# Smart_Plug_Upadated01.net
KiCad netlist of a schematic drawn in Altium Designer
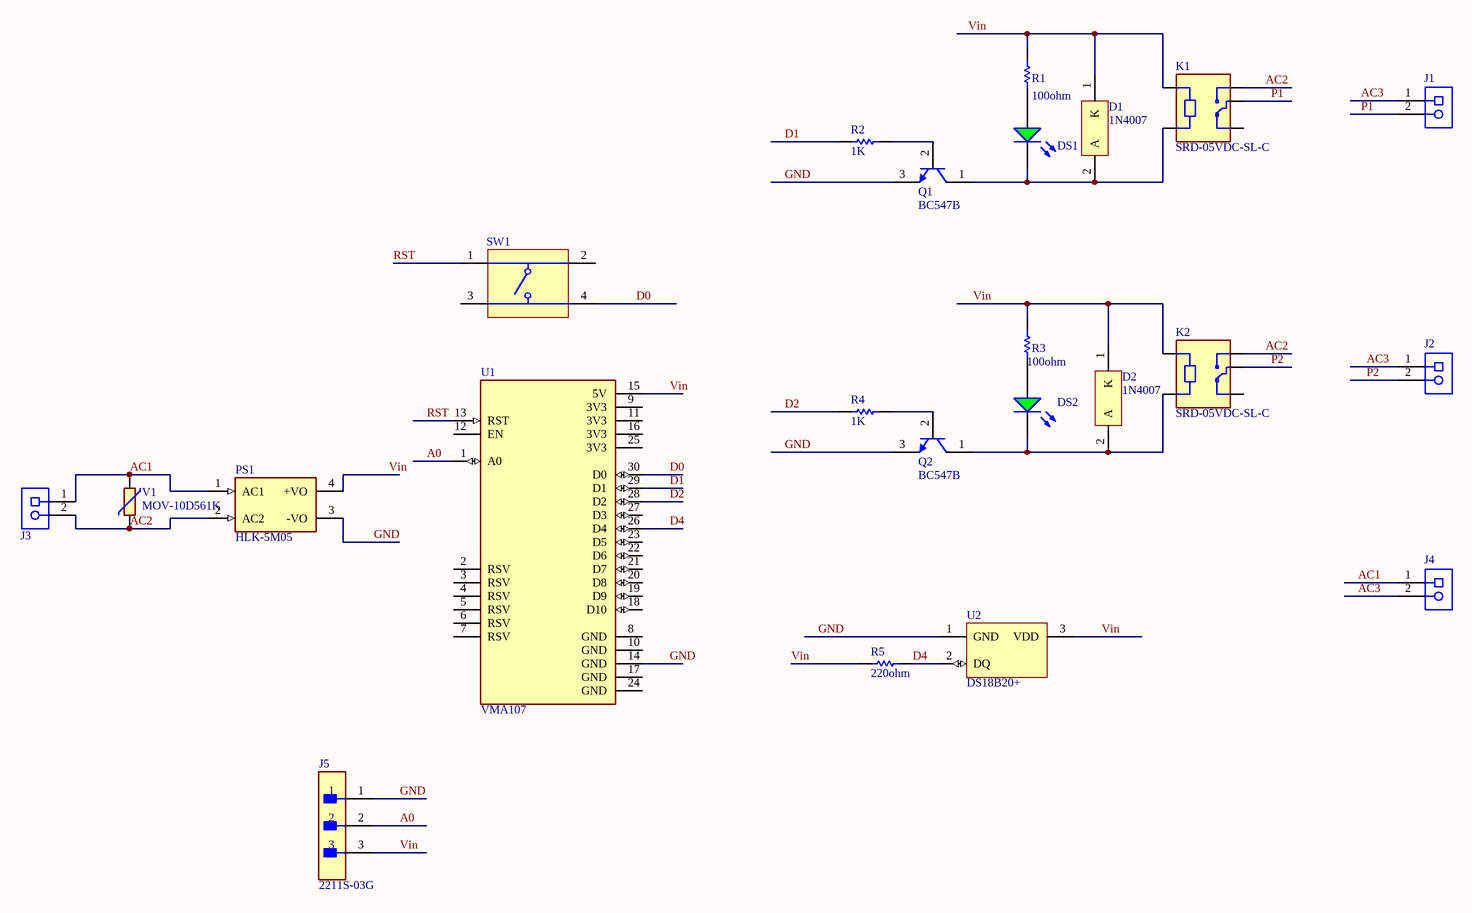
[diagram p0: Smart_Plug(Upadated01).SchDoc]

(export (version "E")
  (design (tool "Eeschema 10.0.6"))
  (components
    (comp (ref "D1")
      (value "1N4007")
      (footprint "ONSC-AXIAL_LEAD-2-59-10_P")
      (description "Standard Recovery Rectifier, 2-Pin Axial_Lead, Pb-Free, Bulk Bag")
      (fields (field (name "MANUFACTURER") "On Semiconductor"))
      (libsource (lib "Altium Content Vault") (part "ONSC-D-K1A2-2_A"))
    )
    (comp (ref "D2")
      (value "1N4007")
      (footprint "ONSC-AXIAL_LEAD-2-59-10_P")
      (description "Standard Recovery Rectifier, 2-Pin Axial_Lead, Pb-Free, Bulk Bag")
      (fields (field (name "MANUFACTURER") "On Semiconductor"))
      (libsource (lib "Altium Content Vault") (part "ONSC-D-K1A2-2_A"))
    )
    (comp (ref "DS1")
      (value "HLMP-3507")
      (footprint "AVAG-HLMP-3507")
      (description "T-1 3/4 (5 mm) Diffused LED Lamp, Green, 2.1 V, -20 to 100 degC, 2-Pin THD, RoHS, Bulk")
      (fields (field (name "MANUFACTURER") "Avago"))
      (libsource (lib "Altium Content Vault") (part "LED-GREEN-AK-2"))
    )
    (comp (ref "DS2")
      (value "HLMP-3507")
      (footprint "AVAG-HLMP-3507")
      (description "T-1 3/4 (5 mm) Diffused LED Lamp, Green, 2.1 V, -20 to 100 degC, 2-Pin THD, RoHS, Bulk")
      (fields (field (name "MANUFACTURER") "Avago"))
      (libsource (lib "Altium Content Vault") (part "LED-GREEN-AK-2"))
    )
    (comp (ref "J1")
      (value "1729128")
      (footprint "PHOE-1729128-2_V")
      (description "PCB Terminal Block, 13.5 A, 400 V, 2-Pin THD, RoHS, Bulk")
      (fields (field (name "MANUFACTURER") "Phoenix Contact"))
      (libsource (lib "Altium Content Vault") (part "CN-2P-F-R2"))
    )
    (comp (ref "J2")
      (value "1729128")
      (footprint "PHOE-1729128-2_V")
      (description "PCB Terminal Block, 13.5 A, 400 V, 2-Pin THD, RoHS, Bulk")
      (fields (field (name "MANUFACTURER") "Phoenix Contact"))
      (libsource (lib "Altium Content Vault") (part "CN-2P-F-R2"))
    )
    (comp (ref "J3")
      (value "1729128")
      (footprint "PHOE-1729128-2_V")
      (description "PCB Terminal Block, 13.5 A, 400 V, 2-Pin THD, RoHS, Bulk")
      (fields (field (name "MANUFACTURER") "Phoenix Contact"))
      (libsource (lib "") (part "CN-2P-F-R2_1"))
    )
    (comp (ref "J4")
      (value "1729128")
      (footprint "PHOE-1729128-2_V")
      (description "PCB Terminal Block, 13.5 A, 400 V, 2-Pin THD, RoHS, Bulk")
      (fields (field (name "MANUFACTURER") "Phoenix Contact"))
      (libsource (lib "Altium Content Vault") (part "CN-2P-F-R2"))
    )
    (comp (ref "J5")
      (value "2211S-03G")
      (footprint "FP-2211S-03G-MFG")
      (libsource (lib "Altium Content Vault") (part "0d3f023dd272f625e17a2be33dea85f"))
    )
    (comp (ref "K1")
      (value "SRD-05VDC-SL-C")
      (footprint "RELAY_SRD-05VDC-SL-C")
      (fields (field (name "MF") "Songle Relay"))
      (libsource (lib "myschlib") (part "SRD-05VDC-SL-C"))
    )
    (comp (ref "K2")
      (value "SRD-05VDC-SL-C")
      (footprint "RELAY_SRD-05VDC-SL-C")
      (fields (field (name "MF") "Songle Relay"))
      (libsource (lib "myschlib") (part "SRD-05VDC-SL-C"))
    )
    (comp (ref "PS1")
      (value "HLK-5M05")
      (footprint "CONV_HLK-5M05")
      (description "AC DC 220V to 5V 5W 5Watt Isolated Switching Step-Down Power Supply Module Converter")
      (fields (field (name "MF") "Hi-link"))
      (libsource (lib "myschlib") (part "HLK-5M05"))
    )
    (comp (ref "Q1")
      (value "BC547B")
      (footprint "ONSC-TO-92-3-29-11")
      (description "Amplifier Transistor, NPN Silicon, 3-Pin TO-92, Bulk Box")
      (fields (field (name "MANUFACTURER") "On Semiconductor"))
      (libsource (lib "Altium Content Vault") (part "ONSC-NPN-C1B2E3-3"))
    )
    (comp (ref "Q2")
      (value "BC547B")
      (footprint "ONSC-TO-92-3-29-11")
      (description "Amplifier Transistor, NPN Silicon, 3-Pin TO-92, Bulk Box")
      (fields (field (name "MANUFACTURER") "On Semiconductor"))
      (libsource (lib "Altium Content Vault") (part "ONSC-NPN-C1B2E3-3"))
    )
    (comp (ref "R1")
      (value "100ohm")
      (footprint "RESA60-630X240")
      (description "Axial Resistor, 100 KOhm, +/- 1%, 0.25 W, -55 to 155 degC, 2-Pin THD, RoHS, Bulk")
      (fields (field (name "TOLERANCE") "1%"))
      (libsource (lib "Altium Content Vault") (part "RES-2"))
    )
    (comp (ref "R2")
      (value "1K")
      (footprint "RESA60-630X240")
      (description "Axial Resistor, 100 KOhm, +/- 1%, 0.25 W, -55 to 155 degC, 2-Pin THD, RoHS, Bulk")
      (fields (field (name "TOLERANCE") "1%"))
      (libsource (lib "Altium Content Vault") (part "RES-2"))
    )
    (comp (ref "R3")
      (value "100ohm")
      (footprint "RESA60-630X240")
      (description "Axial Resistor, 100 KOhm, +/- 1%, 0.25 W, -55 to 155 degC, 2-Pin THD, RoHS, Bulk")
      (fields (field (name "TOLERANCE") "1%"))
      (libsource (lib "Altium Content Vault") (part "RES-2"))
    )
    (comp (ref "R4")
      (value "1K")
      (footprint "RESA60-630X240")
      (description "Axial Resistor, 100 KOhm, +/- 1%, 0.25 W, -55 to 155 degC, 2-Pin THD, RoHS, Bulk")
      (fields (field (name "TOLERANCE") "1%"))
      (libsource (lib "Altium Content Vault") (part "RES-2"))
    )
    (comp (ref "R5")
      (value "220ohm")
      (footprint "RESA60-630X240")
      (description "Axial Resistor, 100 KOhm, +/- 1%, 0.25 W, -55 to 155 degC, 2-Pin THD, RoHS, Bulk")
      (fields (field (name "TOLERANCE") "1%"))
      (libsource (lib "Altium Content Vault") (part "RES-2"))
    )
    (comp (ref "SW1")
      (value "1825910-6")
      (footprint "TECO-1825910-6_V")
      (description "Tact Switch, SPST-NO, 0.05 A, -35 to 85 degC, 4-Pin THD, RoHS, Bulk")
      (fields (field (name "MANUFACTURER") "TE Connectivity"))
      (libsource (lib "Altium Content Vault") (part "SW-SPST-4_A"))
    )
    (comp (ref "U1")
      (value "VMA107")
      (footprint "MODULE_VMA107")
      (description "NodeMCU V2 Lua Based ESP8266 Development Board")
      (fields (field (name "MF") "Velleman"))
      (libsource (lib "myschlib") (part "VMA107"))
    )
    (comp (ref "U2")
      (value "DS18B20+")
      (footprint "Q3+1")
      (libsource (lib "Altium Content Vault") (part "SEN-TEMP-DS1821-SIL3"))
    )
    (comp (ref "V1")
      (value "MOV-10D561K")
      (footprint "MOV-10D561")
      (description "560 V 2.5 kA Varistor 1 Circuit Through Hole Disc 10mm")
      (fields (field (name "MF") "Bourns"))
      (libsource (lib "myschlib") (part "MOV-10D561K"))
    )
  )
  (nets
    (net (code "1") (name "/A0") (class "Default")
      (node (ref "J5") (pin "2") (pinfunction "2_2") (pintype "passive"))
      (node (ref "U1") (pin "1") (pinfunction "A0_1") (pintype "bidirectional"))
    )
    (net (code "2") (name "/AC1") (class "Default")
      (node (ref "J3") (pin "1") (pinfunction "1_1") (pintype "passive"))
      (node (ref "J4") (pin "1") (pinfunction "1_1") (pintype "passive"))
      (node (ref "PS1") (pin "1") (pinfunction "AC1_1") (pintype "input"))
      (node (ref "V1") (pin "1") (pinfunction "1_1") (pintype "passive"))
    )
    (net (code "3") (name "/AC2") (class "Default")
      (node (ref "J3") (pin "2") (pinfunction "2_2") (pintype "passive"))
      (node (ref "K1") (pin "NO") (pinfunction "NO_NO") (pintype "passive"))
      (node (ref "K2") (pin "NO") (pinfunction "NO_NO") (pintype "passive"))
      (node (ref "PS1") (pin "2") (pinfunction "AC2_2") (pintype "input"))
      (node (ref "V1") (pin "2") (pinfunction "2_2") (pintype "passive"))
    )
    (net (code "4") (name "/AC3") (class "Default")
      (node (ref "J1") (pin "1") (pinfunction "1_1") (pintype "passive"))
      (node (ref "J2") (pin "1") (pinfunction "1_1") (pintype "passive"))
      (node (ref "J4") (pin "2") (pinfunction "2_2") (pintype "passive"))
    )
    (net (code "5") (name "/D0") (class "Default")
      (node (ref "SW1") (pin "4") (pinfunction "4_4") (pintype "passive"))
      (node (ref "U1") (pin "30") (pinfunction "D0_30") (pintype "bidirectional"))
    )
    (net (code "6") (name "/D1") (class "Default")
      (node (ref "R2") (pin "1") (pinfunction "1_1") (pintype "passive"))
      (node (ref "U1") (pin "29") (pinfunction "D1_29") (pintype "bidirectional"))
    )
    (net (code "7") (name "/D2") (class "Default")
      (node (ref "R4") (pin "1") (pinfunction "1_1") (pintype "passive"))
      (node (ref "U1") (pin "28") (pinfunction "D2_28") (pintype "bidirectional"))
    )
    (net (code "8") (name "/D4") (class "Default")
      (node (ref "R5") (pin "2") (pinfunction "2_2") (pintype "passive"))
      (node (ref "U1") (pin "26") (pinfunction "D4_26") (pintype "bidirectional"))
      (node (ref "U2") (pin "2") (pinfunction "DQ_2") (pintype "bidirectional"))
    )
    (net (code "9") (name "/GND") (class "Default")
      (node (ref "J5") (pin "1") (pinfunction "1_1") (pintype "passive"))
      (node (ref "PS1") (pin "3") (pinfunction "-VO_3") (pintype "passive"))
      (node (ref "Q1") (pin "3") (pinfunction "E_3") (pintype "passive"))
      (node (ref "Q2") (pin "3") (pinfunction "E_3") (pintype "passive"))
      (node (ref "U1") (pin "14") (pinfunction "GND_14") (pintype "power_in"))
      (node (ref "U2") (pin "1") (pinfunction "GND_1") (pintype "power_in"))
    )
    (net (code "10") (name "/P1") (class "Default")
      (node (ref "J1") (pin "2") (pinfunction "2_2") (pintype "passive"))
      (node (ref "K1") (pin "COM") (pinfunction "COM_COM") (pintype "passive"))
    )
    (net (code "11") (name "/P2") (class "Default")
      (node (ref "J2") (pin "2") (pinfunction "2_2") (pintype "passive"))
      (node (ref "K2") (pin "COM") (pinfunction "COM_COM") (pintype "passive"))
    )
    (net (code "12") (name "/RST") (class "Default")
      (node (ref "SW1") (pin "1") (pinfunction "1_1") (pintype "passive"))
      (node (ref "U1") (pin "13") (pinfunction "RST_13") (pintype "input"))
    )
    (net (code "13") (name "/Vin") (class "Default")
      (node (ref "D1") (pin "1") (pinfunction "K_1") (pintype "passive"))
      (node (ref "D2") (pin "1") (pinfunction "K_1") (pintype "passive"))
      (node (ref "J5") (pin "3") (pinfunction "3_3") (pintype "passive"))
      (node (ref "K1") (pin "A1") (pinfunction "A1_A1") (pintype "passive"))
      (node (ref "K2") (pin "A1") (pinfunction "A1_A1") (pintype "passive"))
      (node (ref "PS1") (pin "4") (pinfunction "+VO_4") (pintype "passive"))
      (node (ref "R1") (pin "1") (pinfunction "1_1") (pintype "passive"))
      (node (ref "R3") (pin "1") (pinfunction "1_1") (pintype "passive"))
      (node (ref "R5") (pin "1") (pinfunction "1_1") (pintype "passive"))
      (node (ref "U1") (pin "15") (pinfunction "5V_15") (pintype "power_in"))
      (node (ref "U2") (pin "3") (pinfunction "VDD_3") (pintype "power_in"))
    )
    (net (code "14") (name "Net-(D1-A)") (class "Default")
      (node (ref "D1") (pin "2") (pinfunction "A_2") (pintype "passive"))
      (node (ref "DS1") (pin "2") (pinfunction "K_2") (pintype "passive"))
      (node (ref "K1") (pin "A2") (pinfunction "A2_A2") (pintype "passive"))
      (node (ref "Q1") (pin "1") (pinfunction "C_1") (pintype "passive"))
    )
    (net (code "15") (name "Net-(D2-A)") (class "Default")
      (node (ref "D2") (pin "2") (pinfunction "A_2") (pintype "passive"))
      (node (ref "DS2") (pin "2") (pinfunction "K_2") (pintype "passive"))
      (node (ref "K2") (pin "A2") (pinfunction "A2_A2") (pintype "passive"))
      (node (ref "Q2") (pin "1") (pinfunction "C_1") (pintype "passive"))
    )
    (net (code "16") (name "Net-(DS1-A)") (class "Default")
      (node (ref "DS1") (pin "1") (pinfunction "A_1") (pintype "passive"))
      (node (ref "R1") (pin "2") (pinfunction "2_2") (pintype "passive"))
    )
    (net (code "17") (name "Net-(DS2-A)") (class "Default")
      (node (ref "DS2") (pin "1") (pinfunction "A_1") (pintype "passive"))
      (node (ref "R3") (pin "2") (pinfunction "2_2") (pintype "passive"))
    )
    (net (code "18") (name "Net-(Q1-B)") (class "Default")
      (node (ref "Q1") (pin "2") (pinfunction "B_2") (pintype "passive"))
      (node (ref "R2") (pin "2") (pinfunction "2_2") (pintype "passive"))
    )
    (net (code "19") (name "Net-(Q2-B)") (class "Default")
      (node (ref "Q2") (pin "2") (pinfunction "B_2") (pintype "passive"))
      (node (ref "R4") (pin "2") (pinfunction "2_2") (pintype "passive"))
    )
    (net (code "20") (name "unconnected-(K1-PadNC)") (class "Default")
      (node (ref "K1") (pin "NC") (pinfunction "NC_NC") (pintype "passive"))
    )
    (net (code "21") (name "unconnected-(K2-PadNC)") (class "Default")
      (node (ref "K2") (pin "NC") (pinfunction "NC_NC") (pintype "passive"))
    )
    (net (code "22") (name "unconnected-(SW1-Pad2)") (class "Default")
      (node (ref "SW1") (pin "2") (pinfunction "2_2") (pintype "passive"))
    )
    (net (code "23") (name "unconnected-(SW1-Pad3)") (class "Default")
      (node (ref "SW1") (pin "3") (pinfunction "3_3") (pintype "passive"))
    )
    (net (code "24") (name "unconnected-(U1-3V3-Pad9)") (class "Default")
      (node (ref "U1") (pin "9") (pinfunction "3V3_9") (pintype "power_in"))
    )
    (net (code "25") (name "unconnected-(U1-3V3-Pad11)") (class "Default")
      (node (ref "U1") (pin "11") (pinfunction "3V3_11") (pintype "power_in"))
    )
    (net (code "26") (name "unconnected-(U1-3V3-Pad16)") (class "Default")
      (node (ref "U1") (pin "16") (pinfunction "3V3_16") (pintype "power_in"))
    )
    (net (code "27") (name "unconnected-(U1-3V3-Pad25)") (class "Default")
      (node (ref "U1") (pin "25") (pinfunction "3V3_25") (pintype "power_in"))
    )
    (net (code "28") (name "unconnected-(U1-D3-Pad27)") (class "Default")
      (node (ref "U1") (pin "27") (pinfunction "D3_27") (pintype "bidirectional"))
    )
    (net (code "29") (name "unconnected-(U1-D5-Pad23)") (class "Default")
      (node (ref "U1") (pin "23") (pinfunction "D5_23") (pintype "bidirectional"))
    )
    (net (code "30") (name "unconnected-(U1-D6-Pad22)") (class "Default")
      (node (ref "U1") (pin "22") (pinfunction "D6_22") (pintype "bidirectional"))
    )
    (net (code "31") (name "unconnected-(U1-D7-Pad21)") (class "Default")
      (node (ref "U1") (pin "21") (pinfunction "D7_21") (pintype "bidirectional"))
    )
    (net (code "32") (name "unconnected-(U1-D8-Pad20)") (class "Default")
      (node (ref "U1") (pin "20") (pinfunction "D8_20") (pintype "bidirectional"))
    )
    (net (code "33") (name "unconnected-(U1-D9-Pad19)") (class "Default")
      (node (ref "U1") (pin "19") (pinfunction "D9_19") (pintype "bidirectional"))
    )
    (net (code "34") (name "unconnected-(U1-D10-Pad18)") (class "Default")
      (node (ref "U1") (pin "18") (pinfunction "D10_18") (pintype "bidirectional"))
    )
    (net (code "35") (name "unconnected-(U1-EN-Pad12)") (class "Default")
      (node (ref "U1") (pin "12") (pinfunction "EN_12") (pintype "passive"))
    )
    (net (code "36") (name "unconnected-(U1-GND-Pad8)") (class "Default")
      (node (ref "U1") (pin "8") (pinfunction "GND_8") (pintype "power_in"))
    )
    (net (code "37") (name "unconnected-(U1-GND-Pad10)") (class "Default")
      (node (ref "U1") (pin "10") (pinfunction "GND_10") (pintype "power_in"))
    )
    (net (code "38") (name "unconnected-(U1-GND-Pad17)") (class "Default")
      (node (ref "U1") (pin "17") (pinfunction "GND_17") (pintype "power_in"))
    )
    (net (code "39") (name "unconnected-(U1-GND-Pad24)") (class "Default")
      (node (ref "U1") (pin "24") (pinfunction "GND_24") (pintype "power_in"))
    )
    (net (code "40") (name "unconnected-(U1-RSV-Pad2)") (class "Default")
      (node (ref "U1") (pin "2") (pinfunction "RSV_2") (pintype "passive"))
    )
    (net (code "41") (name "unconnected-(U1-RSV-Pad3)") (class "Default")
      (node (ref "U1") (pin "3") (pinfunction "RSV_3") (pintype "passive"))
    )
    (net (code "42") (name "unconnected-(U1-RSV-Pad4)") (class "Default")
      (node (ref "U1") (pin "4") (pinfunction "RSV_4") (pintype "passive"))
    )
    (net (code "43") (name "unconnected-(U1-RSV-Pad5)") (class "Default")
      (node (ref "U1") (pin "5") (pinfunction "RSV_5") (pintype "passive"))
    )
    (net (code "44") (name "unconnected-(U1-RSV-Pad6)") (class "Default")
      (node (ref "U1") (pin "6") (pinfunction "RSV_6") (pintype "passive"))
    )
    (net (code "45") (name "unconnected-(U1-RSV-Pad7)") (class "Default")
      (node (ref "U1") (pin "7") (pinfunction "RSV_7") (pintype "passive"))
    )
  )
)
